# Eagle_Light_Sensor.net
KiCad netlist of a schematic drawn in EAGLE
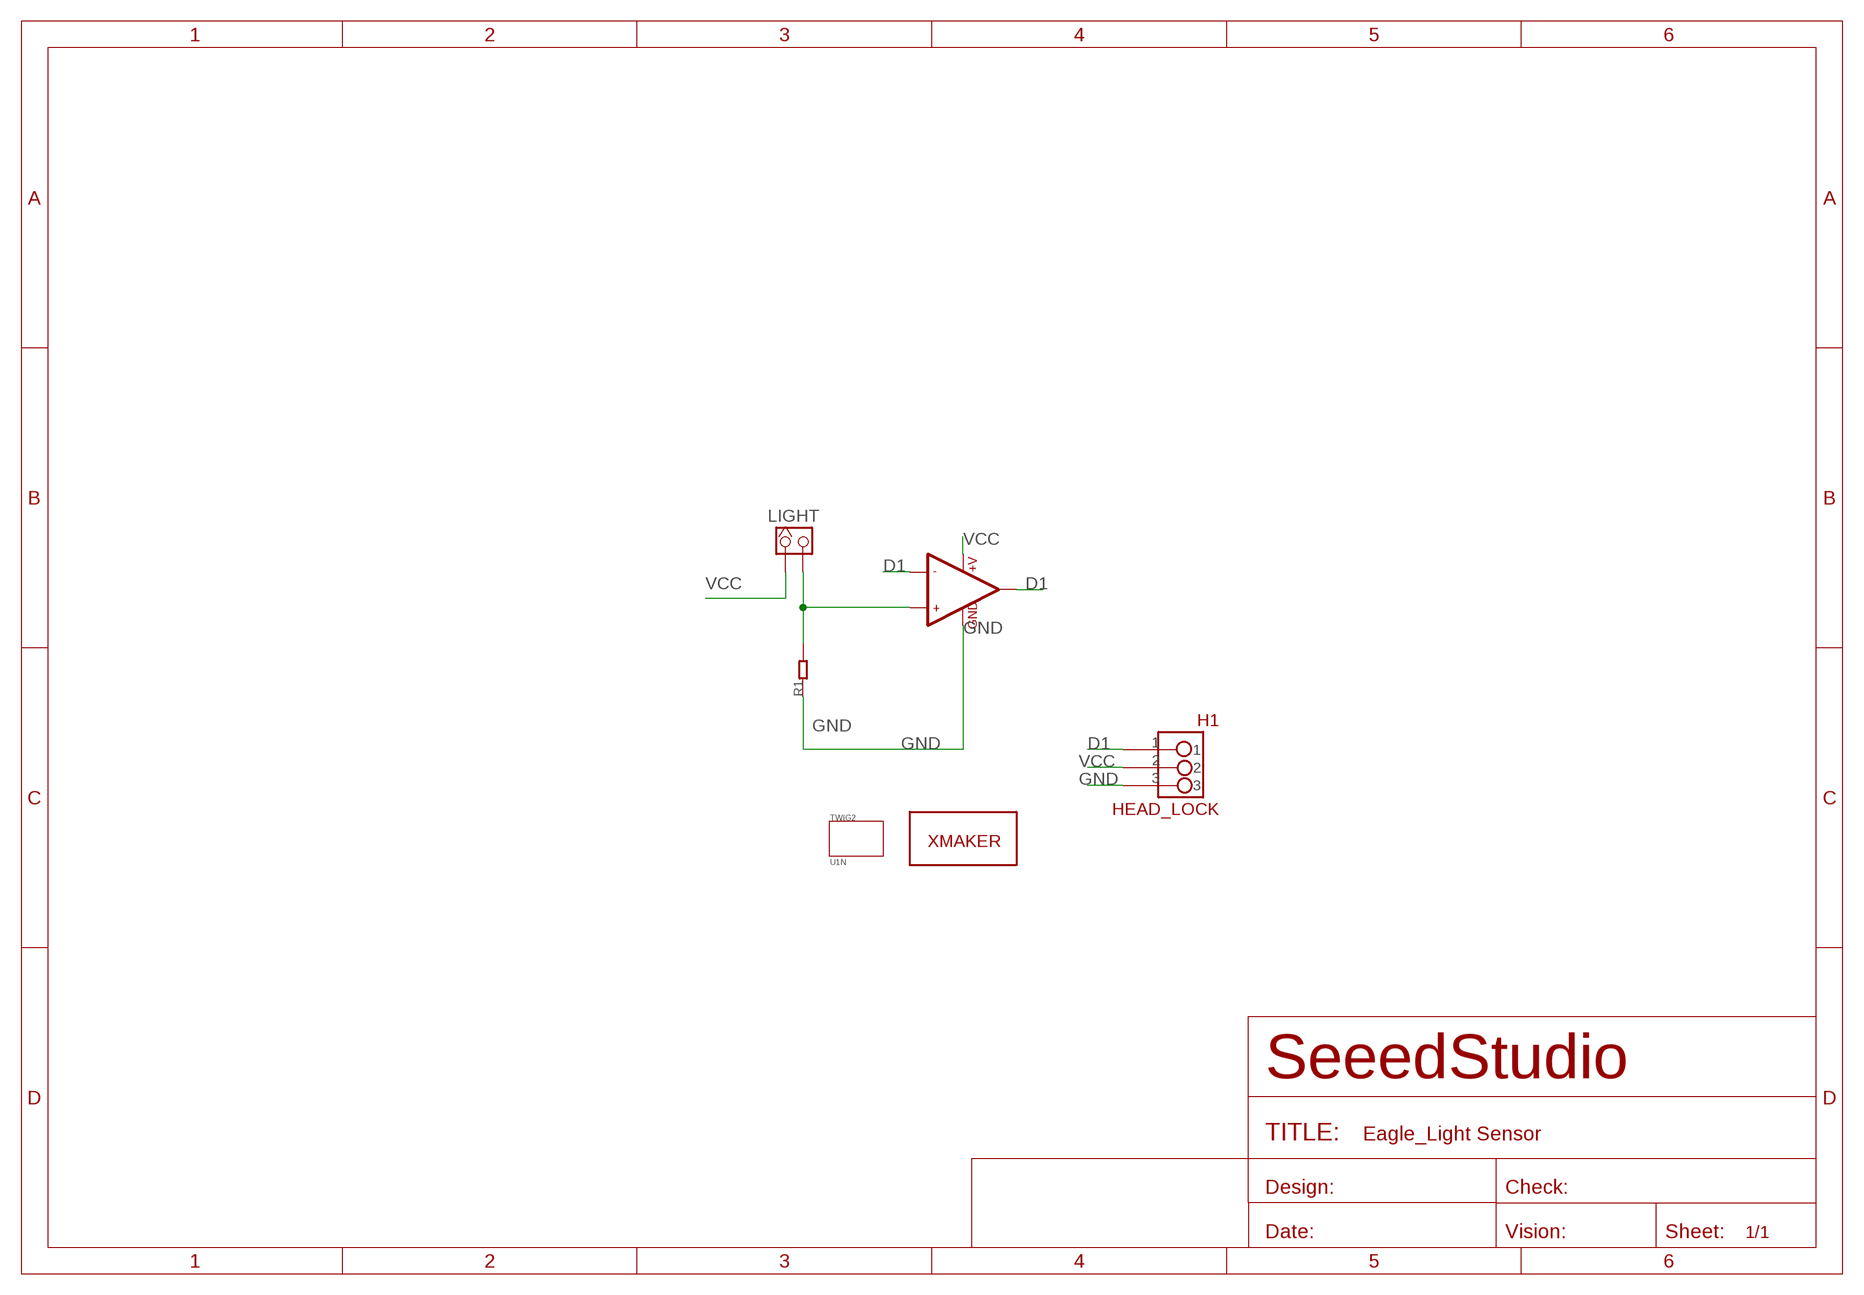
[diagram p0: schematic, sheet 1]

(export (version "E")
  (design (tool "Eeschema 10.0.6"))
  (components
    (comp (ref "H1")
      (value "HEAD_LOCK")
      (footprint "eagle-import:HEAD_LOCK")
      (libsource (lib "eagle-import") (part "HEAD_LOCK"))
    )
    (comp (ref "LIGHT")
      (value "HEADER_1X2_2.54")
      (footprint "eagle-import:CK_1_2")
      (libsource (lib "eagle-import") (part "HEADER_1X2_2.54"))
    )
    (comp (ref "R1")
      (value "R0603")
      (footprint "eagle-import:0603")
      (libsource (lib "eagle-import") (part "R0603"))
    )
    (comp (ref "TWIG2")
      (value "U1N")
      (footprint "eagle-import:U1N")
      (libsource (lib "eagle-import") (part "U1N"))
    )
    (comp (ref "U$1")
      (value "XMAKERLOGO")
      (footprint "eagle-import:XMAKERLOGO")
      (libsource (lib "eagle-import") (part "XMAKERLOGO"))
    )
    (comp (ref "U1")
      (value "LMV358")
      (footprint "eagle-import:SO08")
      (libsource (lib "eagle-import") (part "LMV358"))
    )
  )
  (nets
    (net (code "1") (name "/D1") (class "Default")
      (node (ref "H1") (pin "1") (pinfunction "1_1") (pintype "passive"))
      (node (ref "U1") (pin "1") (pinfunction "OUT1_1") (pintype "output"))
      (node (ref "U1") (pin "2") (pinfunction "-IN1_2") (pintype "input"))
    )
    (net (code "2") (name "/GND") (class "Default")
      (node (ref "H1") (pin "3") (pinfunction "3_3") (pintype "passive"))
      (node (ref "R1") (pin "1") (pinfunction "1_1") (pintype "bidirectional"))
      (node (ref "U1") (pin "4") (pinfunction "GND_4") (pintype "power_in"))
    )
    (net (code "3") (name "/VCC") (class "Default")
      (node (ref "H1") (pin "2") (pinfunction "2_2") (pintype "passive"))
      (node (ref "LIGHT") (pin "1") (pinfunction "1_1") (pintype "bidirectional"))
      (node (ref "U1") (pin "8") (pinfunction "+V_8") (pintype "power_in"))
    )
    (net (code "4") (name "Net-(U1A-+IN1)") (class "Default")
      (node (ref "LIGHT") (pin "2") (pinfunction "2_2") (pintype "bidirectional"))
      (node (ref "R1") (pin "2") (pinfunction "2_2") (pintype "bidirectional"))
      (node (ref "U1") (pin "3") (pinfunction "+IN1_3") (pintype "input"))
    )
  )
)
